# Sheet1.net
KiCad netlist of a schematic drawn in Altium Designer
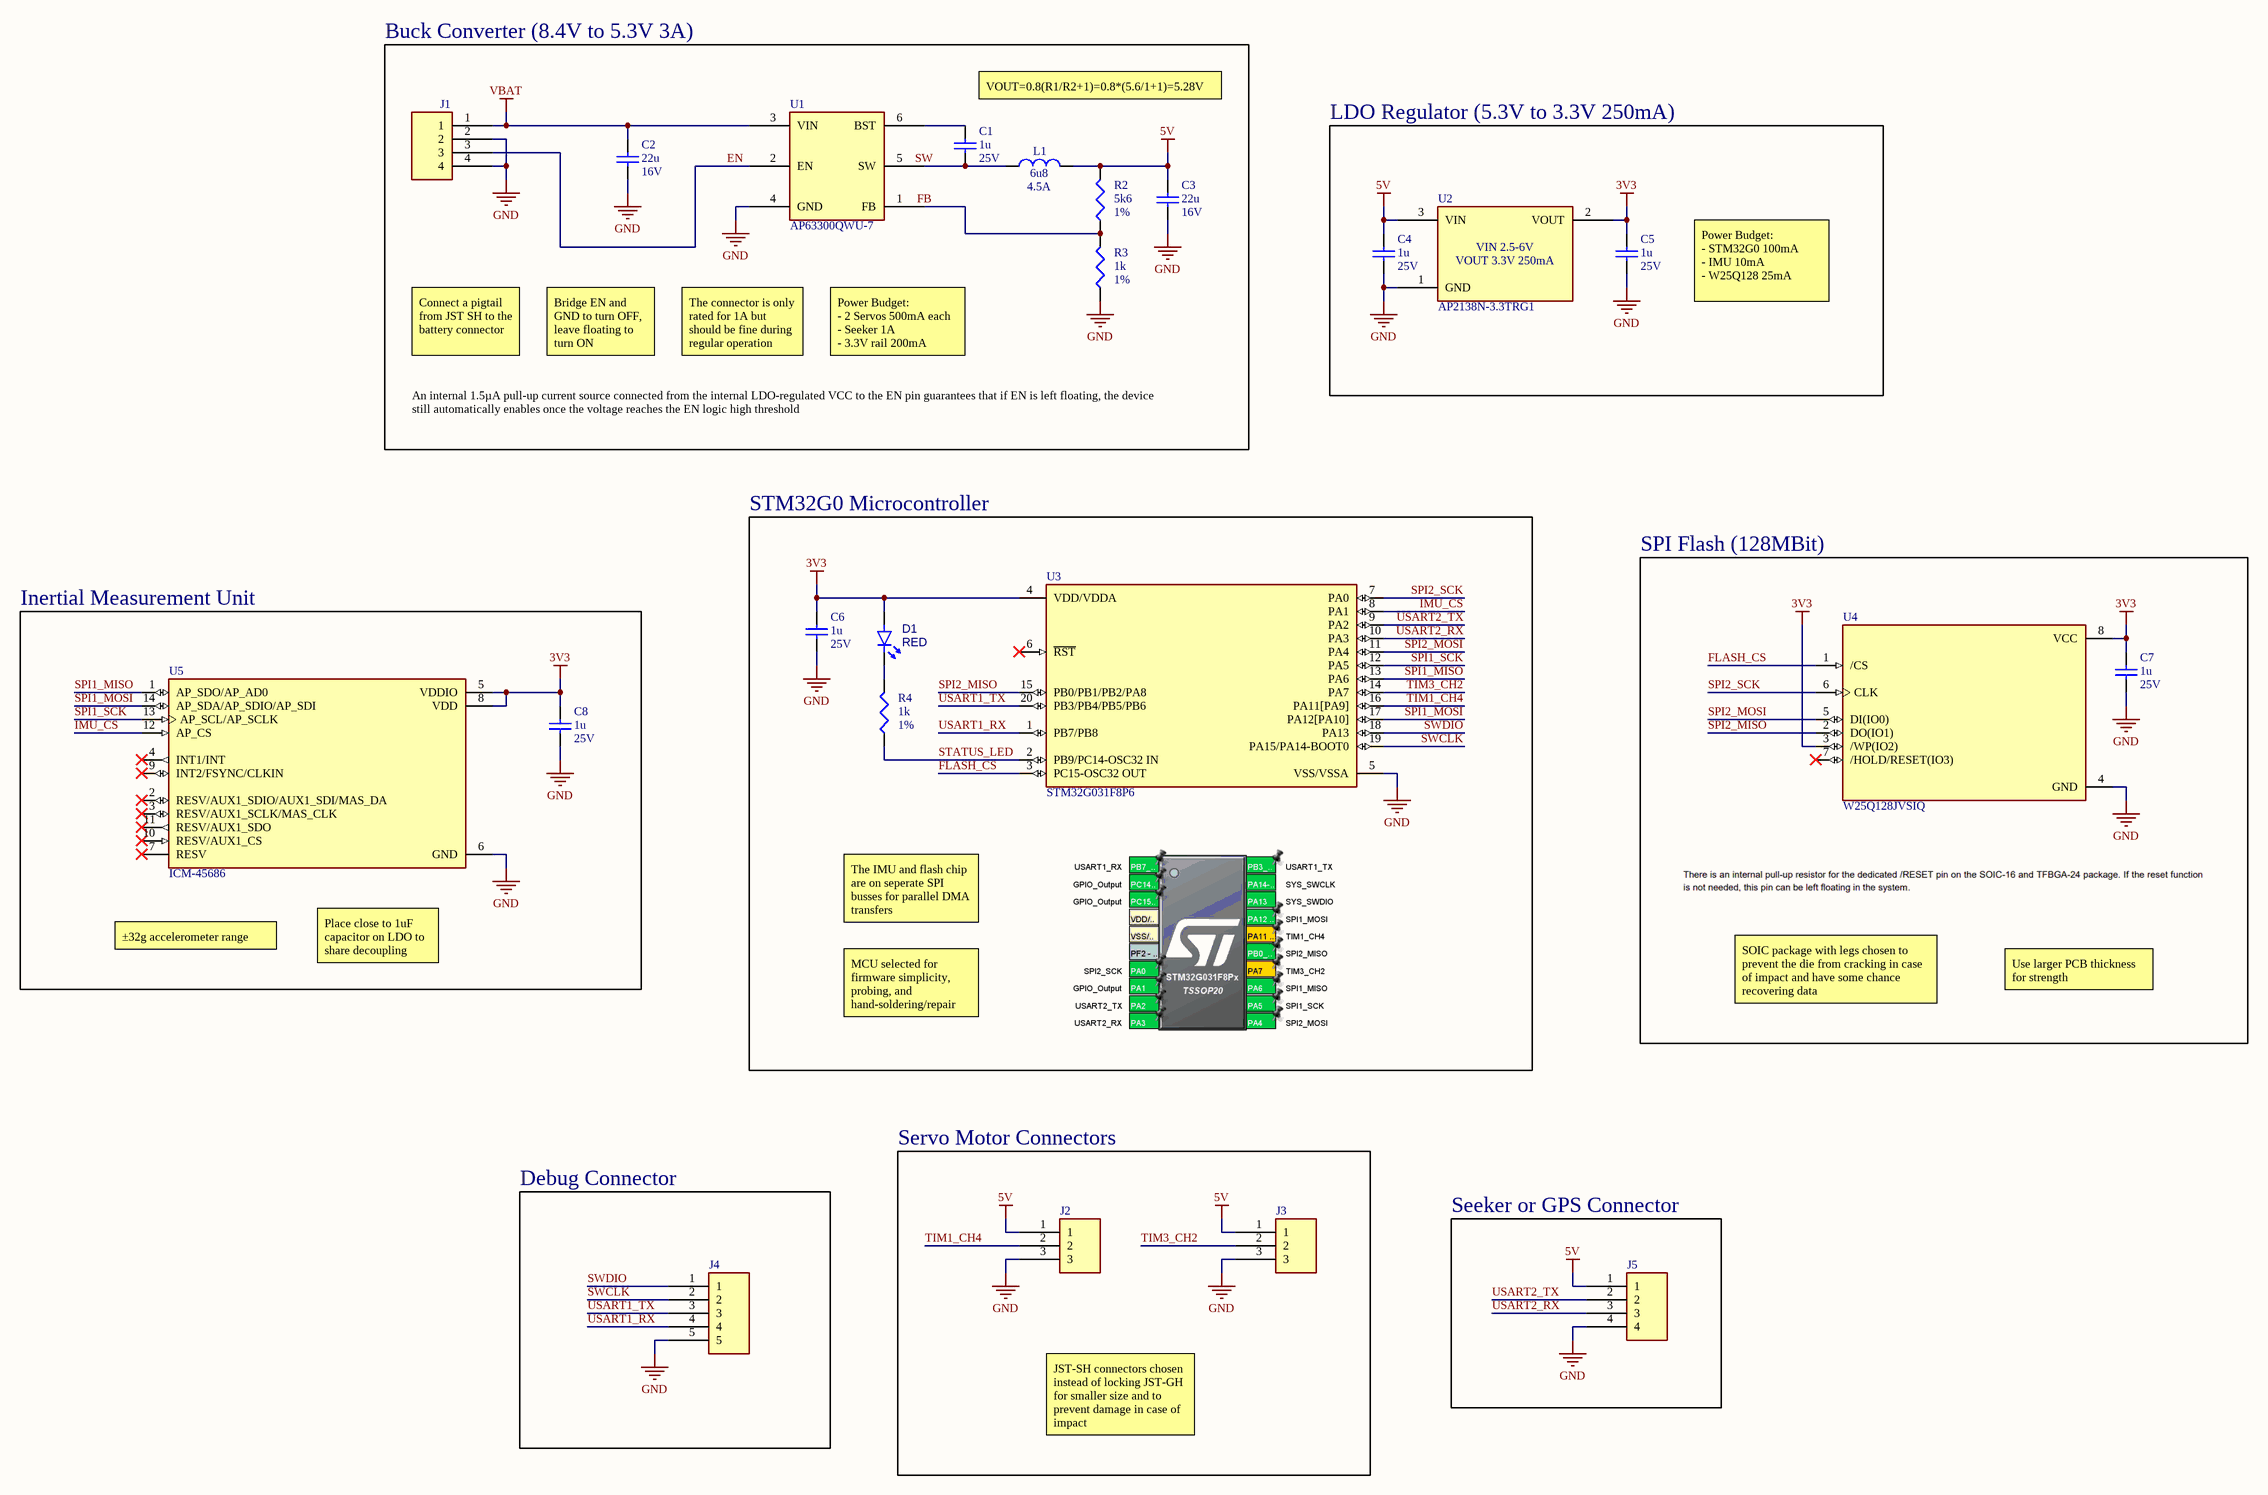
[diagram p0: Sheet1.SchDoc]

(export (version "E")
  (design (tool "Eeschema 10.0.6"))
  (components
    (comp (ref "C1")
      (value "1u")
      (footprint "GRM155R61E105KA12D")
      (description "CAP 1U 25V X5R 0402")
      (fields (field (name "VOLTAGE") "25V") (field (name "Comment") "GRM155R61E105KA12D"))
      (libsource (lib "PersonalAltiumLibrary") (part "GRM155R61E105KA12D"))
    )
    (comp (ref "C2")
      (value "22u")
      (footprint "GRM188R61C226ME01D")
      (description "CAP 22U 16V X5R 0603")
      (fields (field (name "VOLTAGE") "16V") (field (name "Comment") "GRM188R61C226ME01D"))
      (libsource (lib "PersonalAltiumLibrary") (part "GRM188R61C226ME01D"))
    )
    (comp (ref "C3")
      (value "22u")
      (footprint "GRM188R61C226ME01D")
      (description "CAP 22U 16V X5R 0603")
      (fields (field (name "VOLTAGE") "16V") (field (name "Comment") "GRM188R61C226ME01D"))
      (libsource (lib "PersonalAltiumLibrary") (part "GRM188R61C226ME01D"))
    )
    (comp (ref "C4")
      (value "1u")
      (footprint "GRM155R61E105KA12D")
      (description "CAP 1U 25V X5R 0402")
      (fields (field (name "VOLTAGE") "25V") (field (name "Comment") "GRM155R61E105KA12D"))
      (libsource (lib "PersonalAltiumLibrary") (part "GRM155R61E105KA12D"))
    )
    (comp (ref "C5")
      (value "1u")
      (footprint "GRM155R61E105KA12D")
      (description "CAP 1U 25V X5R 0402")
      (fields (field (name "VOLTAGE") "25V") (field (name "Comment") "GRM155R61E105KA12D"))
      (libsource (lib "PersonalAltiumLibrary") (part "GRM155R61E105KA12D"))
    )
    (comp (ref "C6")
      (value "1u")
      (footprint "GRM155R61E105KA12D")
      (description "CAP 1U 25V X5R 0402")
      (fields (field (name "VOLTAGE") "25V") (field (name "Comment") "GRM155R61E105KA12D"))
      (libsource (lib "PersonalAltiumLibrary") (part "GRM155R61E105KA12D"))
    )
    (comp (ref "C7")
      (value "1u")
      (footprint "GRM155R61E105KA12D")
      (description "CAP 1U 25V X5R 0402")
      (fields (field (name "VOLTAGE") "25V") (field (name "Comment") "GRM155R61E105KA12D"))
      (libsource (lib "PersonalAltiumLibrary") (part "GRM155R61E105KA12D"))
    )
    (comp (ref "C8")
      (value "1u")
      (footprint "GRM155R61E105KA12D")
      (description "CAP 1U 25V X5R 0402")
      (fields (field (name "VOLTAGE") "25V") (field (name "Comment") "GRM155R61E105KA12D"))
      (libsource (lib "PersonalAltiumLibrary") (part "GRM155R61E105KA12D"))
    )
    (comp (ref "D1")
      (value "RED")
      (footprint "LTST-C281KRKT")
      (description "LED RED")
      (libsource (lib "PersonalAltiumLibrary") (part "LTST-C281KRKT"))
    )
    (comp (ref "J1")
      (value "SM04B-SRSS-TB")
      (footprint "SM04B-SRSS-TB")
      (description "JST-SH 4P")
      (libsource (lib "PersonalAltiumLibrary") (part "SM04B-SRSS-TB"))
    )
    (comp (ref "J2")
      (value "SM03B-SRSS-TB")
      (footprint "SM03B-SRSS-TB")
      (description "JST-SH 3P")
      (libsource (lib "PersonalAltiumLibrary") (part "SM03B-SRSS-TB"))
    )
    (comp (ref "J3")
      (value "SM03B-SRSS-TB")
      (footprint "SM03B-SRSS-TB")
      (description "JST-SH 3P")
      (libsource (lib "PersonalAltiumLibrary") (part "SM03B-SRSS-TB"))
    )
    (comp (ref "J4")
      (value "SM05B-SRSS-TB")
      (footprint "SM05B-SRSS-TB")
      (description "JST-SH 5P")
      (libsource (lib "PersonalAltiumLibrary") (part "SM05B-SRSS-TB"))
    )
    (comp (ref "J5")
      (value "SM04B-SRSS-TB")
      (footprint "SM04B-SRSS-TB")
      (description "JST-SH 4P")
      (libsource (lib "") (part "SM04B-SRSS-TB_1"))
    )
    (comp (ref "L1")
      (value "6u8")
      (footprint "IHLP2525CZER6R8M01")
      (description "IND 6.8U 4.5A 60m")
      (fields (field (name "CURRENT RATING") "4.5A") (field (name "Comment") "IHLP2525CZER6R8M01"))
      (libsource (lib "PersonalAltiumLibrary") (part "IHLP2525CZER6R8M01"))
    )
    (comp (ref "R2")
      (value "5k6")
      (footprint "RC0402FR-075K6L")
      (description "RES 5.6k 1% 62.5mW 0402")
      (fields (field (name "TOLERANCE") "1%") (field (name "Comment") "RC0402FR-075K6L"))
      (libsource (lib "PersonalAltiumLibrary") (part "RC0402FR-075K6L"))
    )
    (comp (ref "R3")
      (value "1k")
      (footprint "RC0402FR-071KL")
      (description "RES 1k 1% 62.5mW 0402")
      (fields (field (name "TOLERANCE") "1%") (field (name "Comment") "RC0402FR-071KL"))
      (libsource (lib "PersonalAltiumLibrary") (part "RC0402FR-071KL"))
    )
    (comp (ref "R4")
      (value "1k")
      (footprint "RC0402FR-071KL")
      (description "RES 1k 1% 62.5mW 0402")
      (fields (field (name "TOLERANCE") "1%") (field (name "Comment") "RC0402FR-071KL"))
      (libsource (lib "PersonalAltiumLibrary") (part "RC0402FR-071KL"))
    )
    (comp (ref "U1")
      (value "AP63300QWU-7")
      (footprint "AP63300QWU-7")
      (description "BUCK 3A")
      (libsource (lib "PersonalAltiumLibrary") (part "AP63300QWU-7"))
    )
    (comp (ref "U2")
      (value "AP2138N-3.3TRG1")
      (footprint "AP2138N-3.3TRG1")
      (description "LDO 3.3V 250mA")
      (libsource (lib "PersonalAltiumLibrary") (part "AP2138N-3.3TRG1"))
    )
    (comp (ref "U3")
      (value "STM32G031F8P6")
      (footprint "STM32G031F8P6")
      (description "MCU 64MHz 64KB 8KB")
      (libsource (lib "PersonalAltiumLibrary") (part "STM32G031F8P6"))
    )
    (comp (ref "U4")
      (value "W25Q128JVSIQ")
      (footprint "W25Q128JVSIQ")
      (description "FLASH - NOR Memory IC 128Mb (16M x 8) SPI - Quad I/O, QPI, DTR 133 MHz 8-SOIC")
      (fields (field (name "MF") "Winbond Electronics"))
      (libsource (lib "PersonalAltiumLibrary") (part "W25Q128JVSIQ"))
    )
    (comp (ref "U5")
      (value "ICM-45686")
      (footprint "ICM-45686")
      (description "Accelerometer, Gyroscope, 6 Axis Sensor I2C, I3C, SPI Output")
      (libsource (lib "PersonalAltiumLibrary") (part "ICM-45686"))
    )
  )
  (nets
    (net (code "1") (name "/EN") (class "Default")
      (node (ref "J1") (pin "3") (pinfunction "3_3") (pintype "passive"))
      (node (ref "U1") (pin "2") (pinfunction "EN_2") (pintype "passive"))
    )
    (net (code "2") (name "/FB") (class "Default")
      (node (ref "R2") (pin "2") (pinfunction "2_2") (pintype "passive"))
      (node (ref "R3") (pin "1") (pinfunction "1_1") (pintype "passive"))
      (node (ref "U1") (pin "1") (pinfunction "FB_1") (pintype "passive"))
    )
    (net (code "3") (name "/FLASH_CS") (class "Default")
      (node (ref "U3") (pin "3") (pinfunction "PC15-OSC32_OUT_3") (pintype "bidirectional"))
      (node (ref "U4") (pin "1") (pinfunction "/CS_1") (pintype "input"))
    )
    (net (code "4") (name "/IMU_CS") (class "Default")
      (node (ref "U3") (pin "8") (pinfunction "PA1_8") (pintype "bidirectional"))
      (node (ref "U5") (pin "12") (pinfunction "AP_CS_12") (pintype "input"))
    )
    (net (code "5") (name "/SPI1_MISO") (class "Default")
      (node (ref "U3") (pin "13") (pinfunction "PA6_13") (pintype "bidirectional"))
      (node (ref "U5") (pin "1") (pinfunction "AP_SDO/AP_AD0_1") (pintype "bidirectional"))
    )
    (net (code "6") (name "/SPI1_MOSI") (class "Default")
      (node (ref "U3") (pin "17") (pinfunction "PA12[PA10]_17") (pintype "bidirectional"))
      (node (ref "U5") (pin "14") (pinfunction "AP_SDA/AP_SDIO/AP_SDI_14") (pintype "bidirectional"))
    )
    (net (code "7") (name "/SPI1_SCK") (class "Default")
      (node (ref "U3") (pin "12") (pinfunction "PA5_12") (pintype "bidirectional"))
      (node (ref "U5") (pin "13") (pinfunction "AP_SCL/AP_SCLK_13") (pintype "input"))
    )
    (net (code "8") (name "/SPI2_MISO") (class "Default")
      (node (ref "U3") (pin "15") (pinfunction "PB0/PB1/PB2/PA8_15") (pintype "bidirectional"))
      (node (ref "U4") (pin "2") (pinfunction "DO(IO1)_2") (pintype "bidirectional"))
    )
    (net (code "9") (name "/SPI2_MOSI") (class "Default")
      (node (ref "U3") (pin "11") (pinfunction "PA4_11") (pintype "bidirectional"))
      (node (ref "U4") (pin "5") (pinfunction "DI(IO0)_5") (pintype "bidirectional"))
    )
    (net (code "10") (name "/SPI2_SCK") (class "Default")
      (node (ref "U3") (pin "7") (pinfunction "PA0_7") (pintype "bidirectional"))
      (node (ref "U4") (pin "6") (pinfunction "CLK_6") (pintype "input"))
    )
    (net (code "11") (name "/STATUS_LED") (class "Default")
      (node (ref "R4") (pin "2") (pinfunction "2_2") (pintype "passive"))
      (node (ref "U3") (pin "2") (pinfunction "PB9/PC14-OSC32_IN_2") (pintype "bidirectional"))
    )
    (net (code "12") (name "/SW") (class "Default")
      (node (ref "C1") (pin "2") (pinfunction "2_2") (pintype "passive"))
      (node (ref "L1") (pin "1") (pinfunction "1_1") (pintype "passive"))
      (node (ref "U1") (pin "5") (pinfunction "SW_5") (pintype "passive"))
    )
    (net (code "13") (name "/SWCLK") (class "Default")
      (node (ref "J4") (pin "2") (pinfunction "2_2") (pintype "passive"))
      (node (ref "U3") (pin "19") (pinfunction "PA15/PA14-BOOT0_19") (pintype "bidirectional"))
    )
    (net (code "14") (name "/SWDIO") (class "Default")
      (node (ref "J4") (pin "1") (pinfunction "1_1") (pintype "passive"))
      (node (ref "U3") (pin "18") (pinfunction "PA13_18") (pintype "bidirectional"))
    )
    (net (code "15") (name "/TIM1_CH4") (class "Default")
      (node (ref "J2") (pin "2") (pinfunction "2_2") (pintype "passive"))
      (node (ref "U3") (pin "16") (pinfunction "PA11[PA9]_16") (pintype "bidirectional"))
    )
    (net (code "16") (name "/TIM3_CH2") (class "Default")
      (node (ref "J3") (pin "2") (pinfunction "2_2") (pintype "passive"))
      (node (ref "U3") (pin "14") (pinfunction "PA7_14") (pintype "bidirectional"))
    )
    (net (code "17") (name "/USART1_RX") (class "Default")
      (node (ref "J4") (pin "4") (pinfunction "4_4") (pintype "passive"))
      (node (ref "U3") (pin "1") (pinfunction "PB7/PB8_1") (pintype "bidirectional"))
    )
    (net (code "18") (name "/USART1_TX") (class "Default")
      (node (ref "J4") (pin "3") (pinfunction "3_3") (pintype "passive"))
      (node (ref "U3") (pin "20") (pinfunction "PB3/PB4/PB5/PB6_20") (pintype "bidirectional"))
    )
    (net (code "19") (name "/USART2_RX") (class "Default")
      (node (ref "J5") (pin "3") (pinfunction "3_3") (pintype "passive"))
      (node (ref "U3") (pin "10") (pinfunction "PA3_10") (pintype "bidirectional"))
    )
    (net (code "20") (name "/USART2_TX") (class "Default")
      (node (ref "J5") (pin "2") (pinfunction "2_2") (pintype "passive"))
      (node (ref "U3") (pin "9") (pinfunction "PA2_9") (pintype "bidirectional"))
    )
    (net (code "21") (name "3V3") (class "Default")
      (node (ref "C5") (pin "1") (pinfunction "1_1") (pintype "passive"))
      (node (ref "C6") (pin "1") (pinfunction "1_1") (pintype "passive"))
      (node (ref "C7") (pin "1") (pinfunction "1_1") (pintype "passive"))
      (node (ref "C8") (pin "1") (pinfunction "1_1") (pintype "passive"))
      (node (ref "D1") (pin "2") (pinfunction "A_2") (pintype "passive"))
      (node (ref "U2") (pin "2") (pinfunction "VOUT_2") (pintype "passive"))
      (node (ref "U3") (pin "4") (pinfunction "VDD/VDDA_4") (pintype "power_in"))
      (node (ref "U4") (pin "3") (pinfunction "/WP(IO2)_3") (pintype "bidirectional"))
      (node (ref "U4") (pin "8") (pinfunction "VCC_8") (pintype "power_in"))
      (node (ref "U5") (pin "5") (pinfunction "VDDIO_5") (pintype "power_in"))
      (node (ref "U5") (pin "8") (pinfunction "VDD_8") (pintype "power_in"))
    )
    (net (code "22") (name "5V") (class "Default")
      (node (ref "C3") (pin "1") (pinfunction "1_1") (pintype "passive"))
      (node (ref "C4") (pin "1") (pinfunction "1_1") (pintype "passive"))
      (node (ref "J2") (pin "1") (pinfunction "1_1") (pintype "passive"))
      (node (ref "J3") (pin "1") (pinfunction "1_1") (pintype "passive"))
      (node (ref "J5") (pin "1") (pinfunction "1_1") (pintype "passive"))
      (node (ref "L1") (pin "2") (pinfunction "2_2") (pintype "passive"))
      (node (ref "R2") (pin "1") (pinfunction "1_1") (pintype "passive"))
      (node (ref "U2") (pin "3") (pinfunction "VIN_3") (pintype "passive"))
    )
    (net (code "23") (name "GND") (class "Default")
      (node (ref "C2") (pin "2") (pinfunction "2_2") (pintype "passive"))
      (node (ref "C3") (pin "2") (pinfunction "2_2") (pintype "passive"))
      (node (ref "C4") (pin "2") (pinfunction "2_2") (pintype "passive"))
      (node (ref "C5") (pin "2") (pinfunction "2_2") (pintype "passive"))
      (node (ref "C6") (pin "2") (pinfunction "2_2") (pintype "passive"))
      (node (ref "C7") (pin "2") (pinfunction "2_2") (pintype "passive"))
      (node (ref "C8") (pin "2") (pinfunction "2_2") (pintype "passive"))
      (node (ref "J1") (pin "2") (pinfunction "2_2") (pintype "passive"))
      (node (ref "J1") (pin "4") (pinfunction "4_4") (pintype "passive"))
      (node (ref "J2") (pin "3") (pinfunction "3_3") (pintype "passive"))
      (node (ref "J3") (pin "3") (pinfunction "3_3") (pintype "passive"))
      (node (ref "J4") (pin "5") (pinfunction "5_5") (pintype "passive"))
      (node (ref "J5") (pin "4") (pinfunction "4_4") (pintype "passive"))
      (node (ref "R3") (pin "2") (pinfunction "2_2") (pintype "passive"))
      (node (ref "U1") (pin "4") (pinfunction "GND_4") (pintype "passive"))
      (node (ref "U2") (pin "1") (pinfunction "GND_1") (pintype "passive"))
      (node (ref "U3") (pin "5") (pinfunction "VSS/VSSA_5") (pintype "power_in"))
      (node (ref "U4") (pin "4") (pinfunction "GND_4") (pintype "power_in"))
      (node (ref "U5") (pin "6") (pinfunction "GND_6") (pintype "power_in"))
    )
    (net (code "24") (name "Net-(D1-K)") (class "Default")
      (node (ref "D1") (pin "1") (pinfunction "K_1") (pintype "passive"))
      (node (ref "R4") (pin "1") (pinfunction "1_1") (pintype "passive"))
    )
    (net (code "25") (name "Net-(U1-BST)") (class "Default")
      (node (ref "C1") (pin "1") (pinfunction "1_1") (pintype "passive"))
      (node (ref "U1") (pin "6") (pinfunction "BST_6") (pintype "passive"))
    )
    (net (code "26") (name "VBAT") (class "Default")
      (node (ref "C2") (pin "1") (pinfunction "1_1") (pintype "passive"))
      (node (ref "J1") (pin "1") (pinfunction "1_1") (pintype "passive"))
      (node (ref "U1") (pin "3") (pinfunction "VIN_3") (pintype "passive"))
    )
    (net (code "27") (name "unconnected-(U3-~{RST}-Pad6)") (class "Default")
      (node (ref "U3") (pin "6") (pinfunction "~{RST}_6") (pintype "input+no_connect"))
    )
    (net (code "28") (name "unconnected-(U4-{slash}HOLD{slash}RESET(IO3)-Pad7)") (class "Default")
      (node (ref "U4") (pin "7") (pinfunction "/HOLD/RESET(IO3)_7") (pintype "bidirectional+no_connect"))
    )
    (net (code "29") (name "unconnected-(U5-INT1{slash}INT-Pad4)") (class "Default")
      (node (ref "U5") (pin "4") (pinfunction "INT1/INT_4") (pintype "output+no_connect"))
    )
    (net (code "30") (name "unconnected-(U5-INT2{slash}FSYNC{slash}CLKIN-Pad9)") (class "Default")
      (node (ref "U5") (pin "9") (pinfunction "INT2/FSYNC/CLKIN_9") (pintype "bidirectional+no_connect"))
    )
    (net (code "31") (name "unconnected-(U5-RESV-Pad7)") (class "Default")
      (node (ref "U5") (pin "7") (pinfunction "RESV_7") (pintype "passive+no_connect"))
    )
    (net (code "32") (name "unconnected-(U5-RESV{slash}AUX1_CS-Pad10)") (class "Default")
      (node (ref "U5") (pin "10") (pinfunction "RESV/AUX1_CS_10") (pintype "input+no_connect"))
    )
    (net (code "33") (name "unconnected-(U5-RESV{slash}AUX1_SCLK{slash}MAS_CLK-Pad3)") (class "Default")
      (node (ref "U5") (pin "3") (pinfunction "RESV/AUX1_SCLK/MAS_CLK_3") (pintype "bidirectional+no_connect"))
    )
    (net (code "34") (name "unconnected-(U5-RESV{slash}AUX1_SDIO{slash}AUX1_SDI{slash}MAS_DA-Pad2)") (class "Default")
      (node (ref "U5") (pin "2") (pinfunction "RESV/AUX1_SDIO/AUX1_SDI/MAS_DA_2") (pintype "bidirectional+no_connect"))
    )
    (net (code "35") (name "unconnected-(U5-RESV{slash}AUX1_SDO-Pad11)") (class "Default")
      (node (ref "U5") (pin "11") (pinfunction "RESV/AUX1_SDO_11") (pintype "output+no_connect"))
    )
  )
)
